# CHARGER.net
KiCad netlist of a schematic drawn in Altium Designer
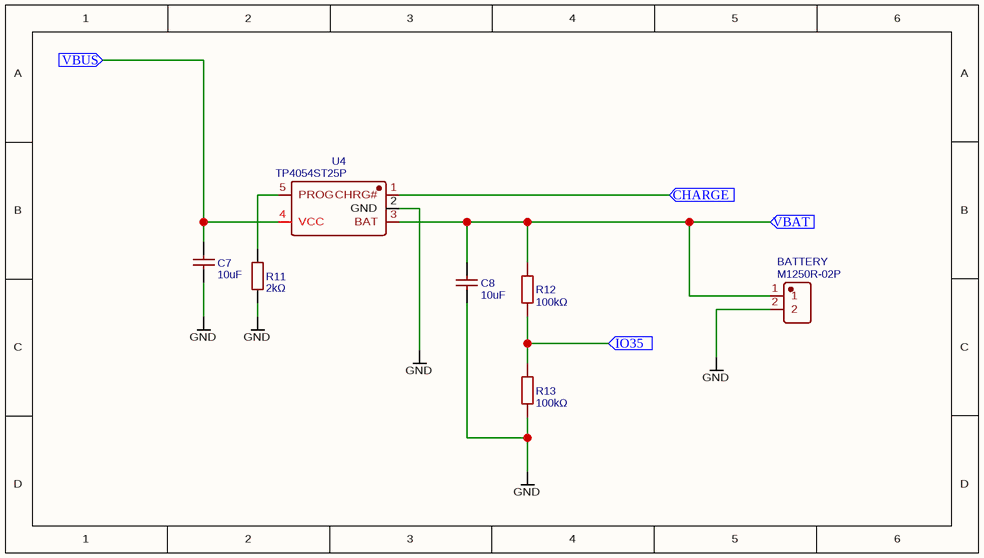
[diagram p0: CHARGER.schdoc]

(export (version "E")
  (design (tool "Eeschema 10.0.6"))
  (components
    (comp (ref "BATTERY")
      (value "M1250R-02P")
      (fields (field (name "BOM_SUPPLIER PART") "C481436") (field (name "CONTRIBUTOR") "LCSC"))
      (libsource (lib "altium-import") (part "root_0_M1250R-02P_"))
    )
    (comp (ref "C7")
      (value "10uF")
      (fields
        (field (name "BOM_MANUFACTURER PART") "CL10A106MO8NQNC")
        (field (name "BOM_SUPPLIER PART") "C92487")
      )
      (libsource (lib "altium-import") (part "root_1_10uF_"))
    )
    (comp (ref "C8")
      (value "10uF")
      (fields
        (field (name "BOM_MANUFACTURER PART") "CL10A106MO8NQNC")
        (field (name "BOM_SUPPLIER PART") "C92487")
      )
      (libsource (lib "altium-import") (part "root_1_10uF_"))
    )
    (comp (ref "R11")
      (value "2kΩ")
      (fields
        (field (name "BOM_MANUFACTURER PART") "RS-03K2001FT")
        (field (name "BOM_SUPPLIER PART") "C115336")
      )
      (libsource (lib "altium-import") (part "root_1_2kΩ_"))
    )
    (comp (ref "R12")
      (value "100kΩ")
      (fields
        (field (name "BOM_MANUFACTURER PART") "RS-03K1003FT")
        (field (name "BOM_SUPPLIER PART") "C115320")
        (field (name "CONTRIBUTOR") "LCSC")
      )
      (libsource (lib "altium-import") (part "root_1_100kΩ_"))
    )
    (comp (ref "R13")
      (value "100kΩ")
      (fields
        (field (name "BOM_MANUFACTURER PART") "RS-03K1003FT")
        (field (name "BOM_SUPPLIER PART") "C115320")
        (field (name "CONTRIBUTOR") "LCSC")
      )
      (libsource (lib "altium-import") (part "root_1_100kΩ_"))
    )
    (comp (ref "U4")
      (value "TP4054ST25P")
      (fields (field (name "BOM_SUPPLIER PART") "C382138") (field (name "CONTRIBUTOR") "LCSC"))
      (libsource (lib "altium-import") (part "root_0_TP4054ST25P_"))
    )
  )
  (nets
    (net (code "1") (name "/CHARGE") (class "Default")
      (node (ref "U4") (pin "1") (pinfunction "CHRG#_1") (pintype "passive"))
    )
    (net (code "2") (name "/IO35") (class "Default")
      (node (ref "R12") (pin "1") (pinfunction "1_1") (pintype "passive"))
      (node (ref "R13") (pin "2") (pinfunction "2_2") (pintype "passive"))
    )
    (net (code "3") (name "/VBAT") (class "Default")
      (node (ref "BATTERY") (pin "1") (pinfunction "1_1") (pintype "passive"))
      (node (ref "C8") (pin "2") (pinfunction "2_2") (pintype "passive"))
      (node (ref "R12") (pin "2") (pinfunction "2_2") (pintype "passive"))
      (node (ref "U4") (pin "3") (pinfunction "BAT_3") (pintype "passive"))
    )
    (net (code "4") (name "/VBUS") (class "Default")
      (node (ref "C7") (pin "2") (pinfunction "2_2") (pintype "passive"))
      (node (ref "U4") (pin "4") (pinfunction "VCC_4") (pintype "passive"))
    )
    (net (code "5") (name "GND") (class "Default")
      (node (ref "BATTERY") (pin "2") (pinfunction "2_2") (pintype "passive"))
      (node (ref "C7") (pin "1") (pinfunction "1_1") (pintype "passive"))
      (node (ref "C8") (pin "1") (pinfunction "1_1") (pintype "passive"))
      (node (ref "R11") (pin "1") (pinfunction "1_1") (pintype "passive"))
      (node (ref "R13") (pin "1") (pinfunction "1_1") (pintype "passive"))
      (node (ref "U4") (pin "2") (pinfunction "GND_2") (pintype "passive"))
    )
    (net (code "6") (name "Net-(U4-PROG)") (class "Default")
      (node (ref "R11") (pin "2") (pinfunction "2_2") (pintype "passive"))
      (node (ref "U4") (pin "5") (pinfunction "PROG_5") (pintype "passive"))
    )
  )
)
